# ESP8266-TFT-PCB.net
KiCad netlist of a schematic drawn in EAGLE
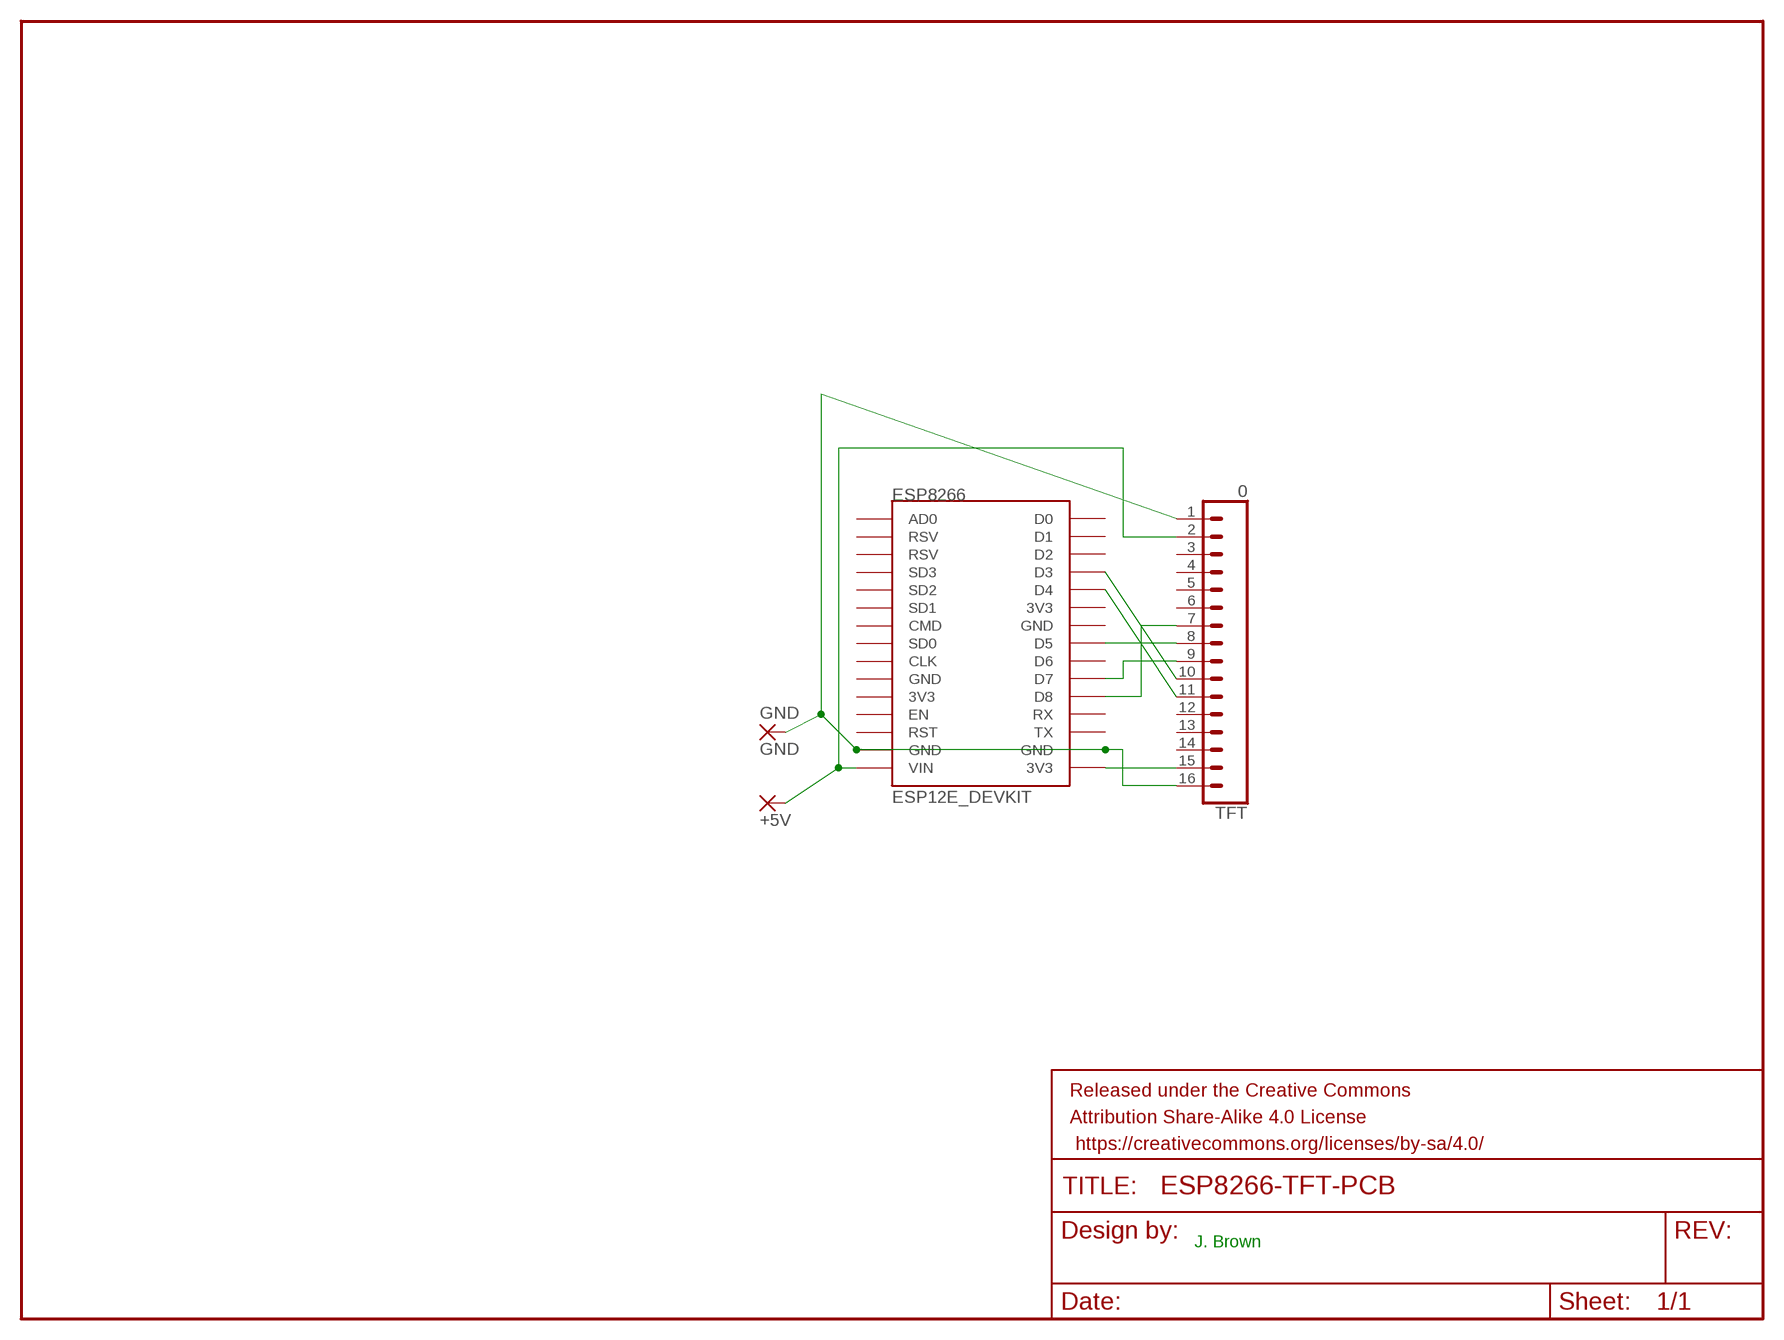
[diagram p0: schematic, sheet 1]

(export (version "E")
  (design (tool "Eeschema 10.0.6"))
  (components
    (comp (ref "ESP8266")
      (value "ESP12E_DEVKIT")
      (footprint "eagle-import:ESP12E_DEVKIT")
      (libsource (lib "eagle-import") (part "ESP12E_DEVKIT"))
    )
    (comp (ref "FRAME1")
      (value "FRAME-LETTER")
      (footprint "eagle-import:CREATIVE_COMMONS")
      (libsource (lib "eagle-import") (part "FRAME-LETTER"))
    )
    (comp (ref "GND")
      (value "GND")
      (footprint "eagle-import:3,81_1,4")
      (libsource (lib "eagle-import") (part "3,81/1,4"))
    )
    (comp (ref "TFT")
      (value "0")
      (footprint "eagle-import:1X16")
      (libsource (lib "eagle-import") (part "CONN_16"))
    )
    (comp (ref "VCC")
      (value "+5V")
      (footprint "eagle-import:3,81_1,4")
      (libsource (lib "eagle-import") (part "3,81/1,4"))
    )
  )
  (nets
    (net (code "1") (name "Net-(ESP8266-3V3-Pad3V3@2)") (class "Default")
      (node (ref "ESP8266") (pin "3V3@2") (pinfunction "3V3_3V3@2") (pintype "bidirectional"))
      (node (ref "TFT") (pin "15") (pinfunction "15_15") (pintype "passive"))
    )
    (net (code "2") (name "Net-(ESP8266-PadD3)") (class "Default")
      (node (ref "ESP8266") (pin "D3") (pinfunction "D3_D3") (pintype "bidirectional"))
      (node (ref "TFT") (pin "10") (pinfunction "10_10") (pintype "passive"))
    )
    (net (code "3") (name "Net-(ESP8266-PadD4)") (class "Default")
      (node (ref "ESP8266") (pin "D4") (pinfunction "D4_D4") (pintype "bidirectional"))
      (node (ref "TFT") (pin "11") (pinfunction "11_11") (pintype "passive"))
    )
    (net (code "4") (name "Net-(ESP8266-PadD5)") (class "Default")
      (node (ref "ESP8266") (pin "D5") (pinfunction "D5_D5") (pintype "bidirectional"))
      (node (ref "TFT") (pin "8") (pinfunction "8_8") (pintype "passive"))
    )
    (net (code "5") (name "Net-(ESP8266-PadD7)") (class "Default")
      (node (ref "ESP8266") (pin "D7") (pinfunction "D7_D7") (pintype "bidirectional"))
      (node (ref "TFT") (pin "9") (pinfunction "9_9") (pintype "passive"))
    )
    (net (code "6") (name "Net-(ESP8266-PadD8)") (class "Default")
      (node (ref "ESP8266") (pin "D8") (pinfunction "D8_D8") (pintype "bidirectional"))
      (node (ref "TFT") (pin "7") (pinfunction "7_7") (pintype "passive"))
    )
    (net (code "7") (name "Net-(GND-P)") (class "Default")
      (node (ref "ESP8266") (pin "GND@1") (pinfunction "GND_GND@1") (pintype "bidirectional"))
      (node (ref "ESP8266") (pin "GND@3") (pinfunction "GND_GND@3") (pintype "bidirectional"))
      (node (ref "GND") (pin "1") (pinfunction "P_1") (pintype "passive"))
      (node (ref "TFT") (pin "1") (pinfunction "1_1") (pintype "passive"))
      (node (ref "TFT") (pin "16") (pinfunction "16_16") (pintype "passive"))
    )
    (net (code "8") (name "Net-(VCC-P)") (class "Default")
      (node (ref "ESP8266") (pin "VIN") (pinfunction "VIN_VIN") (pintype "bidirectional"))
      (node (ref "TFT") (pin "2") (pinfunction "2_2") (pintype "passive"))
      (node (ref "VCC") (pin "1") (pinfunction "P_1") (pintype "passive"))
    )
    (net (code "9") (name "unconnected-(ESP8266-3V3-Pad3V3@0)") (class "Default")
      (node (ref "ESP8266") (pin "3V3@0") (pinfunction "3V3_3V3@0") (pintype "bidirectional"))
    )
    (net (code "10") (name "unconnected-(ESP8266-3V3-Pad3V3@1)") (class "Default")
      (node (ref "ESP8266") (pin "3V3@1") (pinfunction "3V3_3V3@1") (pintype "bidirectional"))
    )
    (net (code "11") (name "unconnected-(ESP8266-GND-PadGND@0)") (class "Default")
      (node (ref "ESP8266") (pin "GND@0") (pinfunction "GND_GND@0") (pintype "bidirectional"))
    )
    (net (code "12") (name "unconnected-(ESP8266-GND-PadGND@2)") (class "Default")
      (node (ref "ESP8266") (pin "GND@2") (pinfunction "GND_GND@2") (pintype "bidirectional"))
    )
    (net (code "13") (name "unconnected-(ESP8266-PadAD0)") (class "Default")
      (node (ref "ESP8266") (pin "AD0") (pinfunction "AD0_AD0") (pintype "bidirectional"))
    )
    (net (code "14") (name "unconnected-(ESP8266-PadCLK)") (class "Default")
      (node (ref "ESP8266") (pin "CLK") (pinfunction "CLK_CLK") (pintype "bidirectional"))
    )
    (net (code "15") (name "unconnected-(ESP8266-PadCMD)") (class "Default")
      (node (ref "ESP8266") (pin "CMD") (pinfunction "CMD_CMD") (pintype "bidirectional"))
    )
    (net (code "16") (name "unconnected-(ESP8266-PadD0)") (class "Default")
      (node (ref "ESP8266") (pin "D0") (pinfunction "D0_D0") (pintype "bidirectional"))
    )
    (net (code "17") (name "unconnected-(ESP8266-PadD1)") (class "Default")
      (node (ref "ESP8266") (pin "D1") (pinfunction "D1_D1") (pintype "bidirectional"))
    )
    (net (code "18") (name "unconnected-(ESP8266-PadD2)") (class "Default")
      (node (ref "ESP8266") (pin "D2") (pinfunction "D2_D2") (pintype "bidirectional"))
    )
    (net (code "19") (name "unconnected-(ESP8266-PadD6)") (class "Default")
      (node (ref "ESP8266") (pin "D6") (pinfunction "D6_D6") (pintype "bidirectional"))
    )
    (net (code "20") (name "unconnected-(ESP8266-PadEN)") (class "Default")
      (node (ref "ESP8266") (pin "EN") (pinfunction "EN_EN") (pintype "bidirectional"))
    )
    (net (code "21") (name "unconnected-(ESP8266-PadRST)") (class "Default")
      (node (ref "ESP8266") (pin "RST") (pinfunction "RST_RST") (pintype "bidirectional"))
    )
    (net (code "22") (name "unconnected-(ESP8266-PadRX)") (class "Default")
      (node (ref "ESP8266") (pin "RX") (pinfunction "RX_RX") (pintype "bidirectional"))
    )
    (net (code "23") (name "unconnected-(ESP8266-PadSD0)") (class "Default")
      (node (ref "ESP8266") (pin "SD0") (pinfunction "SD0_SD0") (pintype "bidirectional"))
    )
    (net (code "24") (name "unconnected-(ESP8266-PadSD1)") (class "Default")
      (node (ref "ESP8266") (pin "SD1") (pinfunction "SD1_SD1") (pintype "bidirectional"))
    )
    (net (code "25") (name "unconnected-(ESP8266-PadSD2)") (class "Default")
      (node (ref "ESP8266") (pin "SD2") (pinfunction "SD2_SD2") (pintype "bidirectional"))
    )
    (net (code "26") (name "unconnected-(ESP8266-PadSD3)") (class "Default")
      (node (ref "ESP8266") (pin "SD3") (pinfunction "SD3_SD3") (pintype "bidirectional"))
    )
    (net (code "27") (name "unconnected-(ESP8266-PadTX)") (class "Default")
      (node (ref "ESP8266") (pin "TX") (pinfunction "TX_TX") (pintype "bidirectional"))
    )
    (net (code "28") (name "unconnected-(ESP8266-RSV-PadRSV@0)") (class "Default")
      (node (ref "ESP8266") (pin "RSV@0") (pinfunction "RSV_RSV@0") (pintype "bidirectional"))
    )
    (net (code "29") (name "unconnected-(ESP8266-RSV-PadRSV@1)") (class "Default")
      (node (ref "ESP8266") (pin "RSV@1") (pinfunction "RSV_RSV@1") (pintype "bidirectional"))
    )
    (net (code "30") (name "unconnected-(TFT-Pad3)") (class "Default")
      (node (ref "TFT") (pin "3") (pinfunction "3_3") (pintype "passive"))
    )
    (net (code "31") (name "unconnected-(TFT-Pad4)") (class "Default")
      (node (ref "TFT") (pin "4") (pinfunction "4_4") (pintype "passive"))
    )
    (net (code "32") (name "unconnected-(TFT-Pad5)") (class "Default")
      (node (ref "TFT") (pin "5") (pinfunction "5_5") (pintype "passive"))
    )
    (net (code "33") (name "unconnected-(TFT-Pad6)") (class "Default")
      (node (ref "TFT") (pin "6") (pinfunction "6_6") (pintype "passive"))
    )
    (net (code "34") (name "unconnected-(TFT-Pad12)") (class "Default")
      (node (ref "TFT") (pin "12") (pinfunction "12_12") (pintype "passive"))
    )
    (net (code "35") (name "unconnected-(TFT-Pad13)") (class "Default")
      (node (ref "TFT") (pin "13") (pinfunction "13_13") (pintype "passive"))
    )
    (net (code "36") (name "unconnected-(TFT-Pad14)") (class "Default")
      (node (ref "TFT") (pin "14") (pinfunction "14_14") (pintype "passive"))
    )
  )
)
